# vco_main.net
KiCad netlist of a schematic drawn in EAGLE
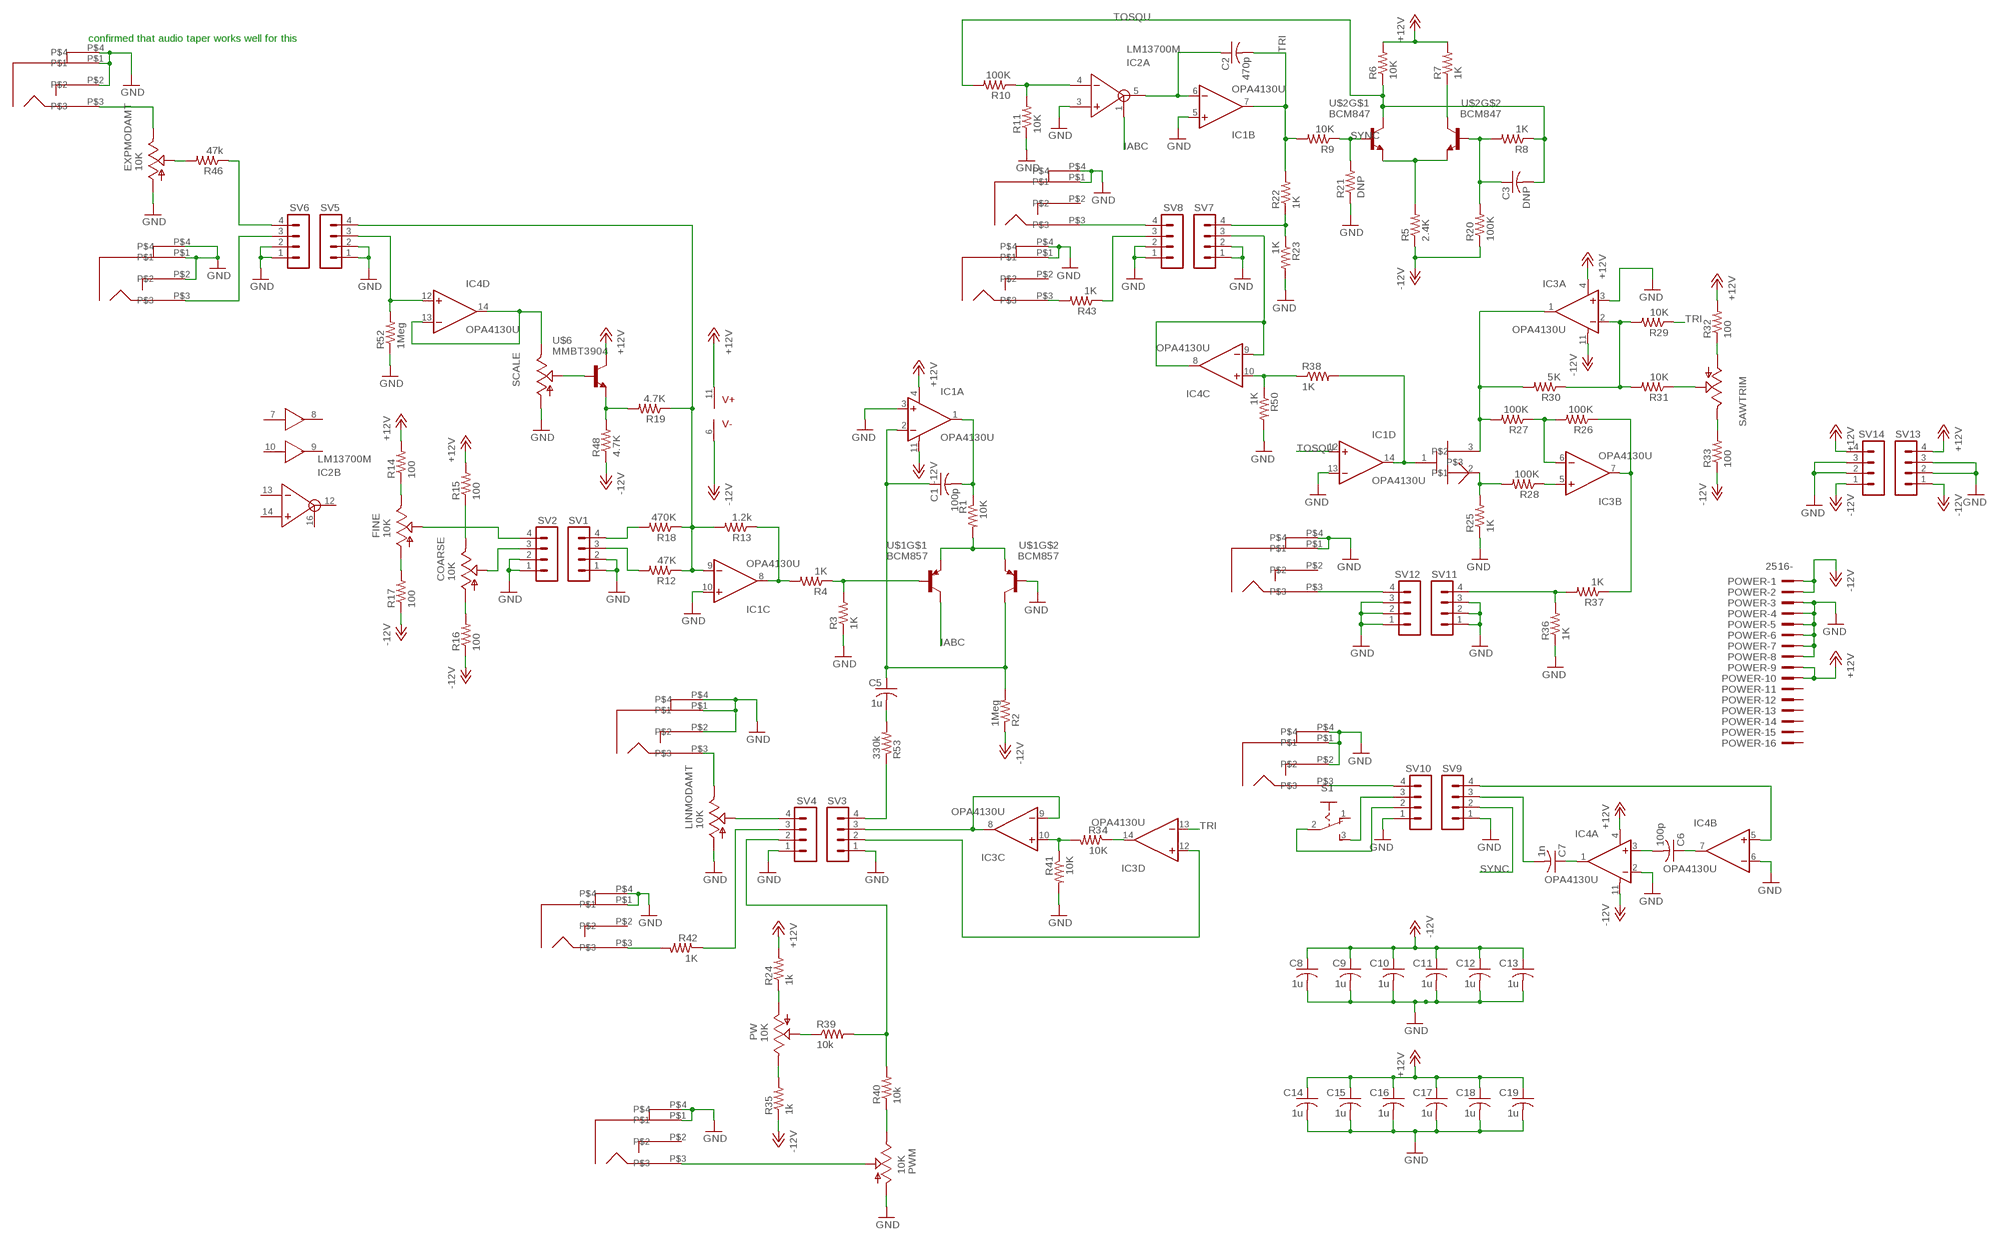
[diagram p0: schematic, sheet 1]

(export (version "E")
  (design (tool "Eeschema 10.0.6"))
  (components
    (comp (ref "C1")
      (value "100p")
      (footprint "eagle-import:C0603")
      (libsource (lib "eagle-import") (part "C-USC0603"))
    )
    (comp (ref "C2")
      (value "470p")
      (footprint "eagle-import:C0603")
      (libsource (lib "eagle-import") (part "C-USC0603"))
    )
    (comp (ref "C3")
      (value "DNP")
      (footprint "eagle-import:C0603")
      (libsource (lib "eagle-import") (part "C-USC0603"))
    )
    (comp (ref "C5")
      (value "1u")
      (footprint "eagle-import:C0603")
      (libsource (lib "eagle-import") (part "C-USC0603"))
    )
    (comp (ref "C6")
      (value "100p")
      (footprint "eagle-import:C0603")
      (libsource (lib "eagle-import") (part "C-USC0603"))
    )
    (comp (ref "C7")
      (value "1n")
      (footprint "eagle-import:C0603")
      (libsource (lib "eagle-import") (part "C-USC0603"))
    )
    (comp (ref "C8")
      (value "1u")
      (footprint "eagle-import:C0603")
      (libsource (lib "eagle-import") (part "C-USC0603"))
    )
    (comp (ref "C9")
      (value "1u")
      (footprint "eagle-import:C0603")
      (libsource (lib "eagle-import") (part "C-USC0603"))
    )
    (comp (ref "C10")
      (value "1u")
      (footprint "eagle-import:C0603")
      (libsource (lib "eagle-import") (part "C-USC0603"))
    )
    (comp (ref "C11")
      (value "1u")
      (footprint "eagle-import:C0603")
      (libsource (lib "eagle-import") (part "C-USC0603"))
    )
    (comp (ref "C12")
      (value "1u")
      (footprint "eagle-import:C0603")
      (libsource (lib "eagle-import") (part "C-USC0603"))
    )
    (comp (ref "C13")
      (value "1u")
      (footprint "eagle-import:C0603")
      (libsource (lib "eagle-import") (part "C-USC0603"))
    )
    (comp (ref "C14")
      (value "1u")
      (footprint "eagle-import:C0603")
      (libsource (lib "eagle-import") (part "C-USC0603"))
    )
    (comp (ref "C15")
      (value "1u")
      (footprint "eagle-import:C0603")
      (libsource (lib "eagle-import") (part "C-USC0603"))
    )
    (comp (ref "C16")
      (value "1u")
      (footprint "eagle-import:C0603")
      (libsource (lib "eagle-import") (part "C-USC0603"))
    )
    (comp (ref "C17")
      (value "1u")
      (footprint "eagle-import:C0603")
      (libsource (lib "eagle-import") (part "C-USC0603"))
    )
    (comp (ref "C18")
      (value "1u")
      (footprint "eagle-import:C0603")
      (libsource (lib "eagle-import") (part "C-USC0603"))
    )
    (comp (ref "C19")
      (value "1u")
      (footprint "eagle-import:C0603")
      (libsource (lib "eagle-import") (part "C-USC0603"))
    )
    (comp (ref "COARSE")
      (value "10K")
      (footprint "eagle-import:EVUFXJ")
      (libsource (lib "eagle-import") (part "US-EVUF2J"))
    )
    (comp (ref "EXPMOD")
      (value "PJ301BM")
      (footprint "eagle-import:PJ301BM")
      (libsource (lib "eagle-import") (part "PJ301BM"))
    )
    (comp (ref "EXPMODAMT")
      (value "10K")
      (footprint "eagle-import:EVUFXJ")
      (libsource (lib "eagle-import") (part "US-EVUF2J"))
    )
    (comp (ref "FINE")
      (value "10K")
      (footprint "eagle-import:EVUFXJ")
      (libsource (lib "eagle-import") (part "US-EVUF2J"))
    )
    (comp (ref "IC1")
      (value "OPA4130U")
      (footprint "eagle-import:SO14")
      (fields (field (name "MF") "TEXAS INSTRUMENTS") (field (name "MPN") "OPA4130UA"))
      (libsource (lib "eagle-import") (part "OPA4130U"))
    )
    (comp (ref "IC2")
      (value "LM13700M")
      (footprint "eagle-import:SO16")
      (libsource (lib "eagle-import") (part "LM13700M"))
    )
    (comp (ref "IC3")
      (value "OPA4130U")
      (footprint "eagle-import:SO14")
      (fields (field (name "MF") "TEXAS INSTRUMENTS") (field (name "MPN") "OPA4130UA"))
      (libsource (lib "eagle-import") (part "OPA4130U"))
    )
    (comp (ref "IC4")
      (value "OPA4130U")
      (footprint "eagle-import:SO14")
      (fields (field (name "MF") "TEXAS INSTRUMENTS") (field (name "MPN") "OPA4130UA"))
      (libsource (lib "eagle-import") (part "OPA4130U"))
    )
    (comp (ref "LINMOD")
      (value "PJ301BM")
      (footprint "eagle-import:PJ301BM")
      (libsource (lib "eagle-import") (part "PJ301BM"))
    )
    (comp (ref "LINMODAMT")
      (value "10K")
      (footprint "eagle-import:EVUFXJ")
      (libsource (lib "eagle-import") (part "US-EVUF2J"))
    )
    (comp (ref "POWER")
      (value "2516-")
      (footprint "eagle-import:PAK100_2500-16")
      (libsource (lib "eagle-import") (part "2516-"))
    )
    (comp (ref "PW")
      (value "10K")
      (footprint "eagle-import:EVUFXJ")
      (libsource (lib "eagle-import") (part "US-EVUF2J"))
    )
    (comp (ref "PWIN")
      (value "PJ301BM")
      (footprint "eagle-import:PJ301BM")
      (libsource (lib "eagle-import") (part "PJ301BM"))
    )
    (comp (ref "PWM")
      (value "10K")
      (footprint "eagle-import:EVUFXJ")
      (libsource (lib "eagle-import") (part "US-EVUF2J"))
    )
    (comp (ref "PWOUT")
      (value "PJ301BM")
      (footprint "eagle-import:PJ301BM")
      (libsource (lib "eagle-import") (part "PJ301BM"))
    )
    (comp (ref "R1")
      (value "10K")
      (footprint "eagle-import:R0603")
      (libsource (lib "eagle-import") (part "R-US_R0603"))
    )
    (comp (ref "R2")
      (value "1Meg")
      (footprint "eagle-import:R0603")
      (libsource (lib "eagle-import") (part "R-US_R0603"))
    )
    (comp (ref "R3")
      (value "1K")
      (footprint "eagle-import:R0603")
      (libsource (lib "eagle-import") (part "R-US_R0603"))
    )
    (comp (ref "R4")
      (value "1K")
      (footprint "eagle-import:R0603")
      (libsource (lib "eagle-import") (part "R-US_R0603"))
    )
    (comp (ref "R5")
      (value "2.4K")
      (footprint "eagle-import:R0603")
      (libsource (lib "eagle-import") (part "R-US_R0603"))
    )
    (comp (ref "R6")
      (value "10K")
      (footprint "eagle-import:R0603")
      (libsource (lib "eagle-import") (part "R-US_R0603"))
    )
    (comp (ref "R7")
      (value "1K")
      (footprint "eagle-import:R0603")
      (libsource (lib "eagle-import") (part "R-US_R0603"))
    )
    (comp (ref "R8")
      (value "1K")
      (footprint "eagle-import:R0603")
      (libsource (lib "eagle-import") (part "R-US_R0603"))
    )
    (comp (ref "R9")
      (value "10K")
      (footprint "eagle-import:R0603")
      (libsource (lib "eagle-import") (part "R-US_R0603"))
    )
    (comp (ref "R10")
      (value "100K")
      (footprint "eagle-import:R0603")
      (libsource (lib "eagle-import") (part "R-US_R0603"))
    )
    (comp (ref "R11")
      (value "10K")
      (footprint "eagle-import:R0603")
      (libsource (lib "eagle-import") (part "R-US_R0603"))
    )
    (comp (ref "R12")
      (value "47K")
      (footprint "eagle-import:R0603")
      (libsource (lib "eagle-import") (part "R-US_R0603"))
    )
    (comp (ref "R13")
      (value "1.2k")
      (footprint "eagle-import:R0603")
      (libsource (lib "eagle-import") (part "R-US_R0603"))
    )
    (comp (ref "R14")
      (value "100")
      (footprint "eagle-import:R0603")
      (libsource (lib "eagle-import") (part "R-US_R0603"))
    )
    (comp (ref "R15")
      (value "100")
      (footprint "eagle-import:R0603")
      (libsource (lib "eagle-import") (part "R-US_R0603"))
    )
    (comp (ref "R16")
      (value "100")
      (footprint "eagle-import:R0603")
      (libsource (lib "eagle-import") (part "R-US_R0603"))
    )
    (comp (ref "R17")
      (value "100")
      (footprint "eagle-import:R0603")
      (libsource (lib "eagle-import") (part "R-US_R0603"))
    )
    (comp (ref "R18")
      (value "470K")
      (footprint "eagle-import:R0603")
      (libsource (lib "eagle-import") (part "R-US_R0603"))
    )
    (comp (ref "R19")
      (value "4.7K")
      (footprint "eagle-import:R0603")
      (libsource (lib "eagle-import") (part "R-US_R0603"))
    )
    (comp (ref "R20")
      (value "100K")
      (footprint "eagle-import:R0603")
      (libsource (lib "eagle-import") (part "R-US_R0603"))
    )
    (comp (ref "R21")
      (value "DNP")
      (footprint "eagle-import:R0603")
      (libsource (lib "eagle-import") (part "R-US_R0603"))
    )
    (comp (ref "R22")
      (value "1K")
      (footprint "eagle-import:R0603")
      (libsource (lib "eagle-import") (part "R-US_R0603"))
    )
    (comp (ref "R23")
      (value "1K")
      (footprint "eagle-import:R0603")
      (libsource (lib "eagle-import") (part "R-US_R0603"))
    )
    (comp (ref "R24")
      (value "1k")
      (footprint "eagle-import:R0603")
      (libsource (lib "eagle-import") (part "R-US_R0603"))
    )
    (comp (ref "R25")
      (value "1K")
      (footprint "eagle-import:R0603")
      (libsource (lib "eagle-import") (part "R-US_R0603"))
    )
    (comp (ref "R26")
      (value "100K")
      (footprint "eagle-import:R0603")
      (libsource (lib "eagle-import") (part "R-US_R0603"))
    )
    (comp (ref "R27")
      (value "100K")
      (footprint "eagle-import:R0603")
      (libsource (lib "eagle-import") (part "R-US_R0603"))
    )
    (comp (ref "R28")
      (value "100K")
      (footprint "eagle-import:R0603")
      (libsource (lib "eagle-import") (part "R-US_R0603"))
    )
    (comp (ref "R29")
      (value "10K")
      (footprint "eagle-import:R0603")
      (libsource (lib "eagle-import") (part "R-US_R0603"))
    )
    (comp (ref "R30")
      (value "5K")
      (footprint "eagle-import:R0603")
      (libsource (lib "eagle-import") (part "R-US_R0603"))
    )
    (comp (ref "R31")
      (value "10K")
      (footprint "eagle-import:R0603")
      (libsource (lib "eagle-import") (part "R-US_R0603"))
    )
    (comp (ref "R32")
      (value "100")
      (footprint "eagle-import:R0603")
      (libsource (lib "eagle-import") (part "R-US_R0603"))
    )
    (comp (ref "R33")
      (value "100")
      (footprint "eagle-import:R0603")
      (libsource (lib "eagle-import") (part "R-US_R0603"))
    )
    (comp (ref "R34")
      (value "10K")
      (footprint "eagle-import:R0603")
      (libsource (lib "eagle-import") (part "R-US_R0603"))
    )
    (comp (ref "R35")
      (value "1k")
      (footprint "eagle-import:R0603")
      (libsource (lib "eagle-import") (part "R-US_R0603"))
    )
    (comp (ref "R36")
      (value "1K")
      (footprint "eagle-import:R0603")
      (libsource (lib "eagle-import") (part "R-US_R0603"))
    )
    (comp (ref "R37")
      (value "1K")
      (footprint "eagle-import:R0603")
      (libsource (lib "eagle-import") (part "R-US_R0603"))
    )
    (comp (ref "R38")
      (value "1K")
      (footprint "eagle-import:R0603")
      (libsource (lib "eagle-import") (part "R-US_R0603"))
    )
    (comp (ref "R39")
      (value "10k")
      (footprint "eagle-import:R0603")
      (libsource (lib "eagle-import") (part "R-US_R0603"))
    )
    (comp (ref "R40")
      (value "10k")
      (footprint "eagle-import:R0603")
      (libsource (lib "eagle-import") (part "R-US_R0603"))
    )
    (comp (ref "R41")
      (value "10K")
      (footprint "eagle-import:R0603")
      (libsource (lib "eagle-import") (part "R-US_R0603"))
    )
    (comp (ref "R42")
      (value "1K")
      (footprint "eagle-import:R0603")
      (libsource (lib "eagle-import") (part "R-US_R0603"))
    )
    (comp (ref "R43")
      (value "1K")
      (footprint "eagle-import:R0603")
      (libsource (lib "eagle-import") (part "R-US_R0603"))
    )
    (comp (ref "R46")
      (value "47k")
      (footprint "eagle-import:R0603")
      (libsource (lib "eagle-import") (part "R-US_R0603"))
    )
    (comp (ref "R48")
      (value "4.7K")
      (footprint "eagle-import:R0603")
      (libsource (lib "eagle-import") (part "R-US_R0603"))
    )
    (comp (ref "R50")
      (value "1K")
      (footprint "eagle-import:R0603")
      (libsource (lib "eagle-import") (part "R-US_R0603"))
    )
    (comp (ref "R52")
      (value "1Meg")
      (footprint "eagle-import:R0603")
      (libsource (lib "eagle-import") (part "R-US_R0603"))
    )
    (comp (ref "R53")
      (value "330k")
      (footprint "eagle-import:R0603")
      (libsource (lib "eagle-import") (part "R-US_R0603"))
    )
    (comp (ref "S1")
      (value "255SB")
      (footprint "eagle-import:255SB")
      (libsource (lib "eagle-import") (part "255SB"))
    )
    (comp (ref "SAW")
      (value "PJ301BM")
      (footprint "eagle-import:PJ301BM")
      (libsource (lib "eagle-import") (part "PJ301BM"))
    )
    (comp (ref "SAWTRIM")
      (value "TRIM_US-B64Y")
      (footprint "eagle-import:B64Y")
      (libsource (lib "eagle-import") (part "TRIM_US-B64Y"))
    )
    (comp (ref "SCALE")
      (value "TRIM_US-B64Y")
      (footprint "eagle-import:B64Y")
      (libsource (lib "eagle-import") (part "TRIM_US-B64Y"))
    )
    (comp (ref "SQUARE")
      (value "PJ301BM")
      (footprint "eagle-import:PJ301BM")
      (libsource (lib "eagle-import") (part "PJ301BM"))
    )
    (comp (ref "SV1")
      (value "MA04-1")
      (footprint "eagle-import:MA04-1")
      (libsource (lib "eagle-import") (part "MA04-1"))
    )
    (comp (ref "SV2")
      (value "MA04-1")
      (footprint "eagle-import:MA04-1")
      (libsource (lib "eagle-import") (part "MA04-1"))
    )
    (comp (ref "SV3")
      (value "MA04-1")
      (footprint "eagle-import:MA04-1")
      (libsource (lib "eagle-import") (part "MA04-1"))
    )
    (comp (ref "SV4")
      (value "MA04-1")
      (footprint "eagle-import:MA04-1")
      (libsource (lib "eagle-import") (part "MA04-1"))
    )
    (comp (ref "SV5")
      (value "MA04-1")
      (footprint "eagle-import:MA04-1")
      (libsource (lib "eagle-import") (part "MA04-1"))
    )
    (comp (ref "SV6")
      (value "MA04-1")
      (footprint "eagle-import:MA04-1")
      (libsource (lib "eagle-import") (part "MA04-1"))
    )
    (comp (ref "SV7")
      (value "MA04-1")
      (footprint "eagle-import:MA04-1")
      (libsource (lib "eagle-import") (part "MA04-1"))
    )
    (comp (ref "SV8")
      (value "MA04-1")
      (footprint "eagle-import:MA04-1")
      (libsource (lib "eagle-import") (part "MA04-1"))
    )
    (comp (ref "SV9")
      (value "MA04-1")
      (footprint "eagle-import:MA04-1")
      (libsource (lib "eagle-import") (part "MA04-1"))
    )
    (comp (ref "SV10")
      (value "MA04-1")
      (footprint "eagle-import:MA04-1")
      (libsource (lib "eagle-import") (part "MA04-1"))
    )
    (comp (ref "SV11")
      (value "MA04-1")
      (footprint "eagle-import:MA04-1")
      (libsource (lib "eagle-import") (part "MA04-1"))
    )
    (comp (ref "SV12")
      (value "MA04-1")
      (footprint "eagle-import:MA04-1")
      (libsource (lib "eagle-import") (part "MA04-1"))
    )
    (comp (ref "SV13")
      (value "MA04-1")
      (footprint "eagle-import:MA04-1")
      (libsource (lib "eagle-import") (part "MA04-1"))
    )
    (comp (ref "SV14")
      (value "MA04-1")
      (footprint "eagle-import:MA04-1")
      (libsource (lib "eagle-import") (part "MA04-1"))
    )
    (comp (ref "SYNC")
      (value "PJ301BM")
      (footprint "eagle-import:PJ301BM")
      (libsource (lib "eagle-import") (part "PJ301BM"))
    )
    (comp (ref "TRIOUT")
      (value "PJ301BM")
      (footprint "eagle-import:PJ301BM")
      (libsource (lib "eagle-import") (part "PJ301BM"))
    )
    (comp (ref "U$1")
      (value "BCM857")
      (footprint "eagle-import:SOT457R_PHILIPS")
      (libsource (lib "eagle-import") (part "BCM857"))
    )
    (comp (ref "U$2")
      (value "BCM847")
      (footprint "eagle-import:SOT457R_PHILIPS")
      (libsource (lib "eagle-import") (part "BCM847"))
    )
    (comp (ref "U$3")
      (value "2N7000")
      (footprint "eagle-import:SOT23")
      (libsource (lib "eagle-import") (part "2N7000"))
    )
    (comp (ref "U$6")
      (value "MMBT3904")
      (footprint "eagle-import:SOT23")
      (libsource (lib "eagle-import") (part "MMBT3904"))
    )
    (comp (ref "VPEROCT")
      (value "PJ301BM")
      (footprint "eagle-import:PJ301BM")
      (libsource (lib "eagle-import") (part "PJ301BM"))
    )
  )
  (nets
    (net (code "1") (name "+12V") (class "Default")
      (node (ref "C14") (pin "1") (pinfunction "1_1") (pintype "passive"))
      (node (ref "C15") (pin "1") (pinfunction "1_1") (pintype "passive"))
      (node (ref "C16") (pin "1") (pinfunction "1_1") (pintype "passive"))
      (node (ref "C17") (pin "1") (pinfunction "1_1") (pintype "passive"))
      (node (ref "C18") (pin "1") (pinfunction "1_1") (pintype "passive"))
      (node (ref "C19") (pin "1") (pinfunction "1_1") (pintype "passive"))
      (node (ref "IC1") (pin "4") (pinfunction "V+_4") (pintype "power_in"))
      (node (ref "IC2") (pin "11") (pinfunction "V+_11") (pintype "bidirectional"))
      (node (ref "IC3") (pin "4") (pinfunction "V+_4") (pintype "power_in"))
      (node (ref "IC4") (pin "4") (pinfunction "V+_4") (pintype "power_in"))
      (node (ref "POWER") (pin "10") (pinfunction "KL_10") (pintype "passive"))
      (node (ref "POWER") (pin "9") (pinfunction "KL_9") (pintype "passive"))
      (node (ref "R14") (pin "2") (pinfunction "2_2") (pintype "passive"))
      (node (ref "R15") (pin "2") (pinfunction "2_2") (pintype "passive"))
      (node (ref "R24") (pin "2") (pinfunction "2_2") (pintype "passive"))
      (node (ref "R32") (pin "2") (pinfunction "2_2") (pintype "passive"))
      (node (ref "R6") (pin "2") (pinfunction "2_2") (pintype "passive"))
      (node (ref "R7") (pin "2") (pinfunction "2_2") (pintype "passive"))
      (node (ref "SV13") (pin "4") (pinfunction "4_4") (pintype "passive"))
      (node (ref "SV14") (pin "4") (pinfunction "4_4") (pintype "passive"))
      (node (ref "U$6") (pin "3") (pinfunction "C_3") (pintype "passive"))
    )
    (net (code "2") (name "-12V") (class "Default")
      (node (ref "C10") (pin "1") (pinfunction "1_1") (pintype "passive"))
      (node (ref "C11") (pin "1") (pinfunction "1_1") (pintype "passive"))
      (node (ref "C12") (pin "1") (pinfunction "1_1") (pintype "passive"))
      (node (ref "C13") (pin "1") (pinfunction "1_1") (pintype "passive"))
      (node (ref "C8") (pin "1") (pinfunction "1_1") (pintype "passive"))
      (node (ref "C9") (pin "1") (pinfunction "1_1") (pintype "passive"))
      (node (ref "IC1") (pin "11") (pinfunction "V-_11") (pintype "power_in"))
      (node (ref "IC2") (pin "6") (pinfunction "V-_6") (pintype "bidirectional"))
      (node (ref "IC3") (pin "11") (pinfunction "V-_11") (pintype "power_in"))
      (node (ref "IC4") (pin "11") (pinfunction "V-_11") (pintype "power_in"))
      (node (ref "POWER") (pin "1") (pinfunction "KL_1") (pintype "passive"))
      (node (ref "POWER") (pin "2") (pinfunction "KL_2") (pintype "passive"))
      (node (ref "R16") (pin "1") (pinfunction "1_1") (pintype "passive"))
      (node (ref "R17") (pin "1") (pinfunction "1_1") (pintype "passive"))
      (node (ref "R2") (pin "1") (pinfunction "1_1") (pintype "passive"))
      (node (ref "R20") (pin "1") (pinfunction "1_1") (pintype "passive"))
      (node (ref "R33") (pin "1") (pinfunction "1_1") (pintype "passive"))
      (node (ref "R35") (pin "1") (pinfunction "1_1") (pintype "passive"))
      (node (ref "R48") (pin "1") (pinfunction "1_1") (pintype "passive"))
      (node (ref "R5") (pin "1") (pinfunction "1_1") (pintype "passive"))
      (node (ref "SV13") (pin "1") (pinfunction "1_1") (pintype "passive"))
      (node (ref "SV14") (pin "1") (pinfunction "1_1") (pintype "passive"))
    )
    (net (code "3") (name "/IABC") (class "Default")
      (node (ref "IC2") (pin "1") (pinfunction "IABC_1") (pintype "bidirectional"))
      (node (ref "U$1") (pin "6") (pinfunction "C_6") (pintype "passive"))
    )
    (net (code "4") (name "/SYNC") (class "Default")
      (node (ref "R21") (pin "2") (pinfunction "2_2") (pintype "passive"))
      (node (ref "R9") (pin "1") (pinfunction "1_1") (pintype "passive"))
      (node (ref "SV9") (pin "2") (pinfunction "2_2") (pintype "passive"))
      (node (ref "U$2") (pin "2") (pinfunction "B_2") (pintype "passive"))
    )
    (net (code "5") (name "/TOSQU") (class "Default")
      (node (ref "C3") (pin "2") (pinfunction "2_2") (pintype "passive"))
      (node (ref "IC1") (pin "12") (pinfunction "+IN_12") (pintype "input"))
      (node (ref "R10") (pin "2") (pinfunction "2_2") (pintype "passive"))
      (node (ref "R6") (pin "1") (pinfunction "1_1") (pintype "passive"))
      (node (ref "R8") (pin "1") (pinfunction "1_1") (pintype "passive"))
      (node (ref "U$2") (pin "6") (pinfunction "C_6") (pintype "passive"))
    )
    (net (code "6") (name "/TRI") (class "Default")
      (node (ref "C2") (pin "2") (pinfunction "2_2") (pintype "passive"))
      (node (ref "IC1") (pin "7") (pinfunction "OUT_7") (pintype "output"))
      (node (ref "IC3") (pin "13") (pinfunction "-IN_13") (pintype "input"))
      (node (ref "R22") (pin "2") (pinfunction "2_2") (pintype "passive"))
      (node (ref "R29") (pin "1") (pinfunction "1_1") (pintype "passive"))
      (node (ref "R9") (pin "2") (pinfunction "2_2") (pintype "passive"))
    )
    (net (code "7") (name "GND") (class "Default")
      (node (ref "C10") (pin "2") (pinfunction "2_2") (pintype "passive"))
      (node (ref "C11") (pin "2") (pinfunction "2_2") (pintype "passive"))
      (node (ref "C12") (pin "2") (pinfunction "2_2") (pintype "passive"))
      (node (ref "C13") (pin "2") (pinfunction "2_2") (pintype "passive"))
      (node (ref "C14") (pin "2") (pinfunction "2_2") (pintype "passive"))
      (node (ref "C15") (pin "2") (pinfunction "2_2") (pintype "passive"))
      (node (ref "C16") (pin "2") (pinfunction "2_2") (pintype "passive"))
      (node (ref "C17") (pin "2") (pinfunction "2_2") (pintype "passive"))
      (node (ref "C18") (pin "2") (pinfunction "2_2") (pintype "passive"))
      (node (ref "C19") (pin "2") (pinfunction "2_2") (pintype "passive"))
      (node (ref "C8") (pin "2") (pinfunction "2_2") (pintype "passive"))
      (node (ref "C9") (pin "2") (pinfunction "2_2") (pintype "passive"))
      (node (ref "EXPMOD") (pin "P$1") (pinfunction "P$1_P$1") (pintype "bidirectional"))
      (node (ref "EXPMOD") (pin "P$2") (pinfunction "P$2_P$2") (pintype "bidirectional"))
      (node (ref "EXPMOD") (pin "P$4") (pinfunction "P$4_P$4") (pintype "bidirectional"))
      (node (ref "EXPMODAMT") (pin "1") (pinfunction "A_1") (pintype "passive"))
      (node (ref "IC1") (pin "10") (pinfunction "+IN_10") (pintype "input"))
      (node (ref "IC1") (pin "13") (pinfunction "-IN_13") (pintype "input"))
      (node (ref "IC1") (pin "3") (pinfunction "+IN_3") (pintype "input"))
      (node (ref "IC1") (pin "5") (pinfunction "+IN_5") (pintype "input"))
      (node (ref "IC2") (pin "3") (pinfunction "+IN_3") (pintype "bidirectional"))
      (node (ref "IC3") (pin "3") (pinfunction "+IN_3") (pintype "input"))
      (node (ref "IC4") (pin "2") (pinfunction "-IN_2") (pintype "input"))
      (node (ref "IC4") (pin "6") (pinfunction "-IN_6") (pintype "input"))
      (node (ref "LINMOD") (pin "P$1") (pinfunction "P$1_P$1") (pintype "bidirectional"))
      (node (ref "LINMOD") (pin "P$2") (pinfunction "P$2_P$2") (pintype "bidirectional"))
      (node (ref "LINMOD") (pin "P$4") (pinfunction "P$4_P$4") (pintype "bidirectional"))
      (node (ref "LINMODAMT") (pin "1") (pinfunction "A_1") (pintype "passive"))
      (node (ref "POWER") (pin "3") (pinfunction "KL_3") (pintype "passive"))
      (node (ref "POWER") (pin "4") (pinfunction "KL_4") (pintype "passive"))
      (node (ref "POWER") (pin "5") (pinfunction "KL_5") (pintype "passive"))
      (node (ref "POWER") (pin "6") (pinfunction "KL_6") (pintype "passive"))
      (node (ref "POWER") (pin "7") (pinfunction "KL_7") (pintype "passive"))
      (node (ref "POWER") (pin "8") (pinfunction "KL_8") (pintype "passive"))
      (node (ref "PWIN") (pin "P$1") (pinfunction "P$1_P$1") (pintype "bidirectional"))
      (node (ref "PWIN") (pin "P$4") (pinfunction "P$4_P$4") (pintype "bidirectional"))
      (node (ref "PWM") (pin "1") (pinfunction "A_1") (pintype "passive"))
      (node (ref "PWOUT") (pin "P$1") (pinfunction "P$1_P$1") (pintype "bidirectional"))
      (node (ref "PWOUT") (pin "P$4") (pinfunction "P$4_P$4") (pintype "bidirectional"))
      (node (ref "R11") (pin "1") (pinfunction "1_1") (pintype "passive"))
      (node (ref "R21") (pin "1") (pinfunction "1_1") (pintype "passive"))
      (node (ref "R23") (pin "2") (pinfunction "2_2") (pintype "passive"))
      (node (ref "R25") (pin "1") (pinfunction "1_1") (pintype "passive"))
      (node (ref "R3") (pin "1") (pinfunction "1_1") (pintype "passive"))
      (node (ref "R36") (pin "1") (pinfunction "1_1") (pintype "passive"))
      (node (ref "R41") (pin "2") (pinfunction "2_2") (pintype "passive"))
      (node (ref "R50") (pin "2") (pinfunction "2_2") (pintype "passive"))
      (node (ref "R52") (pin "1") (pinfunction "1_1") (pintype "passive"))
      (node (ref "SAW") (pin "P$1") (pinfunction "P$1_P$1") (pintype "bidirectional"))
      (node (ref "SAW") (pin "P$4") (pinfunction "P$4_P$4") (pintype "bidirectional"))
      (node (ref "SCALE") (pin "A") (pinfunction "A_A") (pintype "passive"))
      (node (ref "SQUARE") (pin "P$1") (pinfunction "P$1_P$1") (pintype "bidirectional"))
      (node (ref "SQUARE") (pin "P$4") (pinfunction "P$4_P$4") (pintype "bidirectional"))
      (node (ref "SV1") (pin "1") (pinfunction "1_1") (pintype "passive"))
      (node (ref "SV1") (pin "2") (pinfunction "2_2") (pintype "passive"))
      (node (ref "SV10") (pin "1") (pinfunction "1_1") (pintype "passive"))
      (node (ref "SV11") (pin "1") (pinfunction "1_1") (pintype "passive"))
      (node (ref "SV11") (pin "2") (pinfunction "2_2") (pintype "passive"))
      (node (ref "SV11") (pin "3") (pinfunction "3_3") (pintype "passive"))
      (node (ref "SV12") (pin "1") (pinfunction "1_1") (pintype "passive"))
      (node (ref "SV12") (pin "2") (pinfunction "2_2") (pintype "passive"))
      (node (ref "SV12") (pin "3") (pinfunction "3_3") (pintype "passive"))
      (node (ref "SV13") (pin "2") (pinfunction "2_2") (pintype "passive"))
      (node (ref "SV13") (pin "3") (pinfunction "3_3") (pintype "passive"))
      (node (ref "SV14") (pin "2") (pinfunction "2_2") (pintype "passive"))
      (node (ref "SV14") (pin "3") (pinfunction "3_3") (pintype "passive"))
      (node (ref "SV2") (pin "1") (pinfunction "1_1") (pintype "passive"))
      (node (ref "SV2") (pin "2") (pinfunction "2_2") (pintype "passive"))
      (node (ref "SV3") (pin "1") (pinfunction "1_1") (pintype "passive"))
      (node (ref "SV4") (pin "1") (pinfunction "1_1") (pintype "passive"))
      (node (ref "SV5") (pin "1") (pinfunction "1_1") (pintype "passive"))
      (node (ref "SV5") (pin "2") (pinfunction "2_2") (pintype "passive"))
      (node (ref "SV6") (pin "1") (pinfunction "1_1") (pintype "passive"))
      (node (ref "SV6") (pin "2") (pinfunction "2_2") (pintype "passive"))
      (node (ref "SV7") (pin "1") (pinfunction "1_1") (pintype "passive"))
      (node (ref "SV7") (pin "2") (pinfunction "2_2") (pintype "passive"))
      (node (ref "SV8") (pin "1") (pinfunction "1_1") (pintype "passive"))
      (node (ref "SV8") (pin "2") (pinfunction "2_2") (pintype "passive"))
      (node (ref "SV9") (pin "1") (pinfunction "1_1") (pintype "passive"))
      (node (ref "SYNC") (pin "P$1") (pinfunction "P$1_P$1") (pintype "bidirectional"))
      (node (ref "SYNC") (pin "P$2") (pinfunction "P$2_P$2") (pintype "bidirectional"))
      (node (ref "SYNC") (pin "P$4") (pinfunction "P$4_P$4") (pintype "bidirectional"))
      (node (ref "TRIOUT") (pin "P$1") (pinfunction "P$1_P$1") (pintype "bidirectional"))
      (node (ref "TRIOUT") (pin "P$4") (pinfunction "P$4_P$4") (pintype "bidirectional"))
      (node (ref "U$1") (pin "5") (pinfunction "B_5") (pintype "passive"))
      (node (ref "VPEROCT") (pin "P$1") (pinfunction "P$1_P$1") (pintype "bidirectional"))
      (node (ref "VPEROCT") (pin "P$2") (pinfunction "P$2_P$2") (pintype "bidirectional"))
      (node (ref "VPEROCT") (pin "P$4") (pinfunction "P$4_P$4") (pintype "bidirectional"))
    )
    (net (code "8") (name "Net-(C5-Pad2)") (class "Default")
      (node (ref "C5") (pin "2") (pinfunction "2_2") (pintype "passive"))
      (node (ref "R53") (pin "2") (pinfunction "2_2") (pintype "passive"))
    )
    (net (code "9") (name "Net-(C7-Pad2)") (class "Default")
      (node (ref "C7") (pin "2") (pinfunction "2_2") (pintype "passive"))
      (node (ref "SV9") (pin "3") (pinfunction "3_3") (pintype "passive"))
    )
    (net (code "10") (name "Net-(COARSE-A)") (class "Default")
      (node (ref "COARSE") (pin "1") (pinfunction "A_1") (pintype "passive"))
      (node (ref "R16") (pin "2") (pinfunction "2_2") (pintype "passive"))
    )
    (net (code "11") (name "Net-(COARSE-E)") (class "Default")
      (node (ref "COARSE") (pin "3") (pinfunction "E_3") (pintype "passive"))
      (node (ref "R15") (pin "1") (pinfunction "1_1") (pintype "passive"))
    )
    (net (code "12") (name "Net-(COARSE-S)") (class "Default")
      (node (ref "COARSE") (pin "2") (pinfunction "S_2") (pintype "passive"))
      (node (ref "SV2") (pin "3") (pinfunction "3_3") (pintype "passive"))
    )
    (net (code "13") (name "Net-(EXPMODAMT-E)") (class "Default")
      (node (ref "EXPMOD") (pin "P$3") (pinfunction "P$3_P$3") (pintype "bidirectional"))
      (node (ref "EXPMODAMT") (pin "3") (pinfunction "E_3") (pintype "passive"))
    )
    (net (code "14") (name "Net-(EXPMODAMT-S)") (class "Default")
      (node (ref "EXPMODAMT") (pin "2") (pinfunction "S_2") (pintype "passive"))
      (node (ref "R46") (pin "2") (pinfunction "2_2") (pintype "passive"))
    )
    (net (code "15") (name "Net-(FINE-A)") (class "Default")
      (node (ref "FINE") (pin "1") (pinfunction "A_1") (pintype "passive"))
      (node (ref "R17") (pin "2") (pinfunction "2_2") (pintype "passive"))
    )
    (net (code "16") (name "Net-(FINE-E)") (class "Default")
      (node (ref "FINE") (pin "3") (pinfunction "E_3") (pintype "passive"))
      (node (ref "R14") (pin "1") (pinfunction "1_1") (pintype "passive"))
    )
    (net (code "17") (name "Net-(FINE-S)") (class "Default")
      (node (ref "FINE") (pin "2") (pinfunction "S_2") (pintype "passive"))
      (node (ref "SV2") (pin "4") (pinfunction "4_4") (pintype "passive"))
    )
    (net (code "18") (name "Net-(IC1A--IN)") (class "Default")
      (node (ref "C1") (pin "1") (pinfunction "1_1") (pintype "passive"))
      (node (ref "C5") (pin "1") (pinfunction "1_1") (pintype "passive"))
      (node (ref "IC1") (pin "2") (pinfunction "-IN_2") (pintype "input"))
      (node (ref "R2") (pin "2") (pinfunction "2_2") (pintype "passive"))
      (node (ref "U$1") (pin "3") (pinfunction "C_3") (pintype "passive"))
    )
    (net (code "19") (name "Net-(IC1A-OUT)") (class "Default")
      (node (ref "C1") (pin "2") (pinfunction "2_2") (pintype "passive"))
      (node (ref "IC1") (pin "1") (pinfunction "OUT_1") (pintype "output"))
      (node (ref "R1") (pin "1") (pinfunction "1_1") (pintype "passive"))
    )
    (net (code "20") (name "Net-(IC1B--IN)") (class "Default")
      (node (ref "C2") (pin "1") (pinfunction "1_1") (pintype "passive"))
      (node (ref "IC1") (pin "6") (pinfunction "-IN_6") (pintype "input"))
      (node (ref "IC2") (pin "5") (pinfunction "OUT_5") (pintype "bidirectional"))
    )
    (net (code "21") (name "Net-(IC1C--IN)") (class "Default")
      (node (ref "IC1") (pin "9") (pinfunction "-IN_9") (pintype "input"))
      (node (ref "R12") (pin "1") (pinfunction "1_1") (pintype "passive"))
      (node (ref "R13") (pin "2") (pinfunction "2_2") (pintype "passive"))
      (node (ref "R18") (pin "1") (pinfunction "1_1") (pintype "passive"))
      (node (ref "R19") (pin "1") (pinfunction "1_1") (pintype "passive"))
      (node (ref "SV5") (pin "4") (pinfunction "4_4") (pintype "passive"))
    )
    (net (code "22") (name "Net-(IC1C-OUT)") (class "Default")
      (node (ref "IC1") (pin "8") (pinfunction "OUT_8") (pintype "output"))
      (node (ref "R13") (pin "1") (pinfunction "1_1") (pintype "passive"))
      (node (ref "R4") (pin "2") (pinfunction "2_2") (pintype "passive"))
    )
    (net (code "23") (name "Net-(IC1D-OUT)") (class "Default")
      (node (ref "IC1") (pin "14") (pinfunction "OUT_14") (pintype "output"))
      (node (ref "R38") (pin "2") (pinfunction "2_2") (pintype "passive"))
      (node (ref "U$3") (pin "1") (pinfunction "P$3_1") (pintype "bidirectional"))
    )
    (net (code "24") (name "Net-(IC2A--IN)") (class "Default")
      (node (ref "IC2") (pin "4") (pinfunction "-IN_4") (pintype "bidirectional"))
      (node (ref "R10") (pin "1") (pinfunction "1_1") (pintype "passive"))
      (node (ref "R11") (pin "2") (pinfunction "2_2") (pintype "passive"))
    )
    (net (code "25") (name "Net-(IC3A--IN)") (class "Default")
      (node (ref "IC3") (pin "2") (pinfunction "-IN_2") (pintype "input"))
      (node (ref "R29") (pin "2") (pinfunction "2_2") (pintype "passive"))
      (node (ref "R30") (pin "1") (pinfunction "1_1") (pintype "passive"))
      (node (ref "R31") (pin "2") (pinfunction "2_2") (pintype "passive"))
    )
    (net (code "26") (name "Net-(IC3A-OUT)") (class "Default")
      (node (ref "IC3") (pin "1") (pinfunction "OUT_1") (pintype "output"))
      (node (ref "R27") (pin "2") (pinfunction "2_2") (pintype "passive"))
      (node (ref "R30") (pin "2") (pinfunction "2_2") (pintype "passive"))
      (node (ref "U$3") (pin "3") (pinfunction "P$2_3") (pintype "bidirectional"))
    )
    (net (code "27") (name "Net-(IC3B-+IN)") (class "Default")
      (node (ref "IC3") (pin "5") (pinfunction "+IN_5") (pintype "input"))
      (node (ref "R28") (pin "1") (pinfunction "1_1") (pintype "passive"))
    )
    (net (code "28") (name "Net-(IC3B--IN)") (class "Default")
      (node (ref "IC3") (pin "6") (pinfunction "-IN_6") (pintype "input"))
      (node (ref "R26") (pin "2") (pinfunction "2_2") (pintype "passive"))
      (node (ref "R27") (pin "1") (pinfunction "1_1") (pintype "passive"))
    )
    (net (code "29") (name "Net-(IC3B-OUT)") (class "Default")
      (node (ref "IC3") (pin "7") (pinfunction "OUT_7") (pintype "output"))
      (node (ref "R26") (pin "1") (pinfunction "1_1") (pintype "passive"))
      (node (ref "R37") (pin "1") (pinfunction "1_1") (pintype "passive"))
    )
    (net (code "30") (name "Net-(IC3C-+IN)") (class "Default")
      (node (ref "IC3") (pin "10") (pinfunction "+IN_10") (pintype "input"))
      (node (ref "R34") (pin "2") (pinfunction "2_2") (pintype "passive"))
      (node (ref "R41") (pin "1") (pinfunction "1_1") (pintype "passive"))
    )
    (net (code "31") (name "Net-(IC3C--IN)") (class "Default")
      (node (ref "IC3") (pin "8") (pinfunction "OUT_8") (pintype "output"))
      (node (ref "IC3") (pin "9") (pinfunction "-IN_9") (pintype "input"))
      (node (ref "SV3") (pin "3") (pinfunction "3_3") (pintype "passive"))
    )
    (net (code "32") (name "Net-(IC3D-+IN)") (class "Default")
      (node (ref "IC3") (pin "12") (pinfunction "+IN_12") (pintype "input"))
      (node (ref "SV3") (pin "2") (pinfunction "2_2") (pintype "passive"))
    )
    (net (code "33") (name "Net-(IC3D-OUT)") (class "Default")
      (node (ref "IC3") (pin "14") (pinfunction "OUT_14") (pintype "output"))
      (node (ref "R34") (pin "1") (pinfunction "1_1") (pintype "passive"))
    )
    (net (code "34") (name "Net-(IC4A-+IN)") (class "Default")
      (node (ref "C6") (pin "2") (pinfunction "2_2") (pintype "passive"))
      (node (ref "IC4") (pin "3") (pinfunction "+IN_3") (pintype "input"))
    )
    (net (code "35") (name "Net-(IC4A-OUT)") (class "Default")
      (node (ref "C7") (pin "1") (pinfunction "1_1") (pintype "passive"))
      (node (ref "IC4") (pin "1") (pinfunction "OUT_1") (pintype "output"))
    )
    (net (code "36") (name "Net-(IC4B-+IN)") (class "Default")
      (node (ref "IC4") (pin "5") (pinfunction "+IN_5") (pintype "input"))
      (node (ref "SV9") (pin "4") (pinfunction "4_4") (pintype "passive"))
    )
    (net (code "37") (name "Net-(IC4B-OUT)") (class "Default")
      (node (ref "C6") (pin "1") (pinfunction "1_1") (pintype "passive"))
      (node (ref "IC4") (pin "7") (pinfunction "OUT_7") (pintype "output"))
    )
    (net (code "38") (name "Net-(IC4C-+IN)") (class "Default")
      (node (ref "IC4") (pin "10") (pinfunction "+IN_10") (pintype "input"))
      (node (ref "R38") (pin "1") (pinfunction "1_1") (pintype "passive"))
      (node (ref "R50") (pin "1") (pinfunction "1_1") (pintype "passive"))
    )
    (net (code "39") (name "Net-(IC4C--IN)") (class "Default")
      (node (ref "IC4") (pin "8") (pinfunction "OUT_8") (pintype "output"))
      (node (ref "IC4") (pin "9") (pinfunction "-IN_9") (pintype "input"))
      (node (ref "SV7") (pin "3") (pinfunction "3_3") (pintype "passive"))
    )
    (net (code "40") (name "Net-(IC4D-+IN)") (class "Default")
      (node (ref "IC4") (pin "12") (pinfunction "+IN_12") (pintype "input"))
      (node (ref "R52") (pin "2") (pinfunction "2_2") (pintype "passive"))
      (node (ref "SV5") (pin "3") (pinfunction "3_3") (pintype "passive"))
    )
    (net (code "41") (name "Net-(IC4D--IN)") (class "Default")
      (node (ref "IC4") (pin "13") (pinfunction "-IN_13") (pintype "input"))
      (node (ref "IC4") (pin "14") (pinfunction "OUT_14") (pintype "output"))
      (node (ref "SCALE") (pin "E") (pinfunction "E_E") (pintype "passive"))
    )
    (net (code "42") (name "Net-(LINMODAMT-E)") (class "Default")
      (node (ref "LINMOD") (pin "P$3") (pinfunction "P$3_P$3") (pintype "bidirectional"))
      (node (ref "LINMODAMT") (pin "3") (pinfunction "E_3") (pintype "passive"))
    )
    (net (code "43") (name "Net-(LINMODAMT-S)") (class "Default")
      (node (ref "LINMODAMT") (pin "2") (pinfunction "S_2") (pintype "passive"))
      (node (ref "SV4") (pin "4") (pinfunction "4_4") (pintype "passive"))
    )
    (net (code "44") (name "Net-(PW-A)") (class "Default")
      (node (ref "PW") (pin "1") (pinfunction "A_1") (pintype "passive"))
      (node (ref "R24") (pin "1") (pinfunction "1_1") (pintype "passive"))
    )
    (net (code "45") (name "Net-(PW-E)") (class "Default")
      (node (ref "PW") (pin "3") (pinfunction "E_3") (pintype "passive"))
      (node (ref "R35") (pin "2") (pinfunction "2_2") (pintype "passive"))
    )
    (net (code "46") (name "Net-(PW-S)") (class "Default")
      (node (ref "PW") (pin "2") (pinfunction "S_2") (pintype "passive"))
      (node (ref "R39") (pin "1") (pinfunction "1_1") (pintype "passive"))
    )
    (net (code "47") (name "Net-(PWM-E)") (class "Default")
      (node (ref "PWM") (pin "3") (pinfunction "E_3") (pintype "passive"))
      (node (ref "R40") (pin "1") (pinfunction "1_1") (pintype "passive"))
    )
    (net (code "48") (name "Net-(PWM-S)") (class "Default")
      (node (ref "PWIN") (pin "P$3") (pinfunction "P$3_P$3") (pintype "bidirectional"))
      (node (ref "PWM") (pin "2") (pinfunction "S_2") (pintype "passive"))
    )
    (net (code "49") (name "Net-(PWOUT-PadP$3)") (class "Default")
      (node (ref "PWOUT") (pin "P$3") (pinfunction "P$3_P$3") (pintype "bidirectional"))
      (node (ref "R42") (pin "2") (pinfunction "2_2") (pintype "passive"))
    )
    (net (code "50") (name "Net-(R12-Pad2)") (class "Default")
      (node (ref "R12") (pin "2") (pinfunction "2_2") (pintype "passive"))
      (node (ref "SV1") (pin "3") (pinfunction "3_3") (pintype "passive"))
    )
    (net (code "51") (name "Net-(R18-Pad2)") (class "Default")
      (node (ref "R18") (pin "2") (pinfunction "2_2") (pintype "passive"))
      (node (ref "SV1") (pin "4") (pinfunction "4_4") (pintype "passive"))
    )
    (net (code "52") (name "Net-(R22-Pad1)") (class "Default")
      (node (ref "R22") (pin "1") (pinfunction "1_1") (pintype "passive"))
      (node (ref "R23") (pin "1") (pinfunction "1_1") (pintype "passive"))
      (node (ref "SV7") (pin "4") (pinfunction "4_4") (pintype "passive"))
    )
    (net (code "53") (name "Net-(R31-Pad1)") (class "Default")
      (node (ref "R31") (pin "1") (pinfunction "1_1") (pintype "passive"))
      (node (ref "SAWTRIM") (pin "S") (pinfunction "S_S") (pintype "passive"))
    )
    (net (code "54") (name "Net-(R32-Pad1)") (class "Default")
      (node (ref "R32") (pin "1") (pinfunction "1_1") (pintype "passive"))
      (node (ref "SAWTRIM") (pin "A") (pinfunction "A_A") (pintype "passive"))
    )
    (net (code "55") (name "Net-(R33-Pad2)") (class "Default")
      (node (ref "R33") (pin "2") (pinfunction "2_2") (pintype "passive"))
      (node (ref "SAWTRIM") (pin "E") (pinfunction "E_E") (pintype "passive"))
    )
    (net (code "56") (name "Net-(R36-Pad2)") (class "Default")
      (node (ref "R36") (pin "2") (pinfunction "2_2") (pintype "passive"))
      (node (ref "R37") (pin "2") (pinfunction "2_2") (pintype "passive"))
      (node (ref "SV11") (pin "4") (pinfunction "4_4") (pintype "passive"))
    )
    (net (code "57") (name "Net-(R39-Pad2)") (class "Default")
      (node (ref "R39") (pin "2") (pinfunction "2_2") (pintype "passive"))
      (node (ref "R40") (pin "2") (pinfunction "2_2") (pintype "passive"))
      (node (ref "SV4") (pin "2") (pinfunction "2_2") (pintype "passive"))
    )
    (net (code "58") (name "Net-(R42-Pad1)") (class "Default")
      (node (ref "R42") (pin "1") (pinfunction "1_1") (pintype "passive"))
      (node (ref "SV4") (pin "3") (pinfunction "3_3") (pintype "passive"))
    )
    (net (code "59") (name "Net-(R43-Pad1)") (class "Default")
      (node (ref "R43") (pin "1") (pinfunction "1_1") (pintype "passive"))
      (node (ref "SV8") (pin "3") (pinfunction "3_3") (pintype "passive"))
    )
    (net (code "60") (name "Net-(R43-Pad2)") (class "Default")
      (node (ref "R43") (pin "2") (pinfunction "2_2") (pintype "passive"))
      (node (ref "SQUARE") (pin "P$3") (pinfunction "P$3_P$3") (pintype "bidirectional"))
    )
    (net (code "61") (name "Net-(R46-Pad1)") (class "Default")
      (node (ref "R46") (pin "1") (pinfunction "1_1") (pintype "passive"))
      (node (ref "SV6") (pin "4") (pinfunction "4_4") (pintype "passive"))
    )
    (net (code "62") (name "Net-(R53-Pad1)") (class "Default")
      (node (ref "R53") (pin "1") (pinfunction "1_1") (pintype "passive"))
      (node (ref "SV3") (pin "4") (pinfunction "4_4") (pintype "passive"))
    )
    (net (code "63") (name "Net-(S1-P)") (class "Default")
      (node (ref "S1") (pin "2") (pinfunction "P_2") (pintype "passive"))
      (node (ref "SV10") (pin "2") (pinfunction "2_2") (pintype "passive"))
    )
    (net (code "64") (name "Net-(S1-S)") (class "Default")
      (node (ref "S1") (pin "3") (pinfunction "S_3") (pintype "passive"))
      (node (ref "SV10") (pin "3") (pinfunction "3_3") (pintype "passive"))
    )
    (net (code "65") (name "Net-(SAW-PadP$3)") (class "Default")
      (node (ref "SAW") (pin "P$3") (pinfunction "P$3_P$3") (pintype "bidirectional"))
      (node (ref "SV12") (pin "4") (pinfunction "4_4") (pintype "passive"))
    )
    (net (code "66") (name "Net-(SV6-Pad3)") (class "Default")
      (node (ref "SV6") (pin "3") (pinfunction "3_3") (pintype "passive"))
      (node (ref "VPEROCT") (pin "P$3") (pinfunction "P$3_P$3") (pintype "bidirectional"))
    )
    (net (code "67") (name "Net-(SV8-Pad4)") (class "Default")
      (node (ref "SV8") (pin "4") (pinfunction "4_4") (pintype "passive"))
      (node (ref "TRIOUT") (pin "P$3") (pinfunction "P$3_P$3") (pintype "bidirectional"))
    )
    (net (code "68") (name "Net-(SV10-Pad4)") (class "Default")
      (node (ref "SV10") (pin "4") (pinfunction "4_4") (pintype "passive"))
      (node (ref "SYNC") (pin "P$3") (pinfunction "P$3_P$3") (pintype "bidirectional"))
    )
    (net (code "69") (name "Net-(U$1A-B)") (class "Default")
      (node (ref "R3") (pin "2") (pinfunction "2_2") (pintype "passive"))
      (node (ref "R4") (pin "1") (pinfunction "1_1") (pintype "passive"))
      (node (ref "U$1") (pin "2") (pinfunction "B_2") (pintype "passive"))
    )
    (net (code "70") (name "Net-(U$1A-E)") (class "Default")
      (node (ref "R1") (pin "2") (pinfunction "2_2") (pintype "passive"))
      (node (ref "U$1") (pin "1") (pinfunction "E_1") (pintype "passive"))
      (node (ref "U$1") (pin "4") (pinfunction "E_4") (pintype "passive"))
    )
    (net (code "71") (name "Net-(U$2A-E)") (class "Default")
      (node (ref "R5") (pin "2") (pinfunction "2_2") (pintype "passive"))
      (node (ref "U$2") (pin "1") (pinfunction "E_1") (pintype "passive"))
      (node (ref "U$2") (pin "4") (pinfunction "E_4") (pintype "passive"))
    )
    (net (code "72") (name "Net-(U$2B-B)") (class "Default")
      (node (ref "C3") (pin "1") (pinfunction "1_1") (pintype "passive"))
      (node (ref "R20") (pin "2") (pinfunction "2_2") (pintype "passive"))
      (node (ref "R8") (pin "2") (pinfunction "2_2") (pintype "passive"))
      (node (ref "U$2") (pin "5") (pinfunction "B_5") (pintype "passive"))
    )
    (net (code "73") (name "Net-(U$2B-C)") (class "Default")
      (node (ref "R7") (pin "1") (pinfunction "1_1") (pintype "passive"))
      (node (ref "U$2") (pin "3") (pinfunction "C_3") (pintype "passive"))
    )
    (net (code "74") (name "Net-(U$3-P$1)") (class "Default")
      (node (ref "R25") (pin "2") (pinfunction "2_2") (pintype "passive"))
      (node (ref "R28") (pin "2") (pinfunction "2_2") (pintype "passive"))
      (node (ref "U$3") (pin "2") (pinfunction "P$1_2") (pintype "bidirectional"))
    )
    (net (code "75") (name "Net-(U$6-B)") (class "Default")
      (node (ref "SCALE") (pin "S") (pinfunction "S_S") (pintype "passive"))
      (node (ref "U$6") (pin "1") (pinfunction "B_1") (pintype "passive"))
    )
    (net (code "76") (name "Net-(U$6-E)") (class "Default")
      (node (ref "R19") (pin "2") (pinfunction "2_2") (pintype "passive"))
      (node (ref "R48") (pin "2") (pinfunction "2_2") (pintype "passive"))
      (node (ref "U$6") (pin "2") (pinfunction "E_2") (pintype "passive"))
    )
    (net (code "77") (name "unconnected-(IC2B-+IN-Pad14)") (class "Default")
      (node (ref "IC2") (pin "14") (pinfunction "+IN_14") (pintype "bidirectional"))
    )
    (net (code "78") (name "unconnected-(IC2B--IN-Pad13)") (class "Default")
      (node (ref "IC2") (pin "13") (pinfunction "-IN_13") (pintype "bidirectional"))
    )
    (net (code "79") (name "unconnected-(IC2B-IABC-Pad16)") (class "Default")
      (node (ref "IC2") (pin "16") (pinfunction "IABC_16") (pintype "bidirectional"))
    )
    (net (code "80") (name "unconnected-(IC2B-OUT-Pad12)") (class "Default")
      (node (ref "IC2") (pin "12") (pinfunction "OUT_12") (pintype "bidirectional"))
    )
    (net (code "81") (name "unconnected-(IC2C-IN-Pad7)") (class "Default")
      (node (ref "IC2") (pin "7") (pinfunction "IN_7") (pintype "bidirectional"))
    )
    (net (code "82") (name "unconnected-(IC2C-OUT-Pad8)") (class "Default")
      (node (ref "IC2") (pin "8") (pinfunction "OUT_8") (pintype "bidirectional"))
    )
    (net (code "83") (name "unconnected-(IC2D-IN-Pad10)") (class "Default")
      (node (ref "IC2") (pin "10") (pinfunction "IN_10") (pintype "bidirectional"))
    )
    (net (code "84") (name "unconnected-(IC2D-OUT-Pad9)") (class "Default")
      (node (ref "IC2") (pin "9") (pinfunction "OUT_9") (pintype "bidirectional"))
    )
    (net (code "85") (name "unconnected-(POWERC-KL-Pad11)") (class "Default")
      (node (ref "POWER") (pin "11") (pinfunction "KL_11") (pintype "passive"))
    )
    (net (code "86") (name "unconnected-(POWERD-KL-Pad12)") (class "Default")
      (node (ref "POWER") (pin "12") (pinfunction "KL_12") (pintype "passive"))
    )
    (net (code "87") (name "unconnected-(POWERE-KL-Pad13)") (class "Default")
      (node (ref "POWER") (pin "13") (pinfunction "KL_13") (pintype "passive"))
    )
    (net (code "88") (name "unconnected-(POWERF-KL-Pad14)") (class "Default")
      (node (ref "POWER") (pin "14") (pinfunction "KL_14") (pintype "passive"))
    )
    (net (code "89") (name "unconnected-(POWERG-KL-Pad15)") (class "Default")
      (node (ref "POWER") (pin "15") (pinfunction "KL_15") (pintype "passive"))
    )
    (net (code "90") (name "unconnected-(POWERH-KL-Pad16)") (class "Default")
      (node (ref "POWER") (pin "16") (pinfunction "KL_16") (pintype "passive"))
    )
    (net (code "91") (name "unconnected-(PWIN-PadP$2)") (class "Default")
      (node (ref "PWIN") (pin "P$2") (pinfunction "P$2_P$2") (pintype "bidirectional"))
    )
    (net (code "92") (name "unconnected-(PWOUT-PadP$2)") (class "Default")
      (node (ref "PWOUT") (pin "P$2") (pinfunction "P$2_P$2") (pintype "bidirectional"))
    )
    (net (code "93") (name "unconnected-(S1-O-Pad1)") (class "Default")
      (node (ref "S1") (pin "1") (pinfunction "O_1") (pintype "passive"))
    )
    (net (code "94") (name "unconnected-(SAW-PadP$2)") (class "Default")
      (node (ref "SAW") (pin "P$2") (pinfunction "P$2_P$2") (pintype "bidirectional"))
    )
    (net (code "95") (name "unconnected-(SQUARE-PadP$2)") (class "Default")
      (node (ref "SQUARE") (pin "P$2") (pinfunction "P$2_P$2") (pintype "bidirectional"))
    )
    (net (code "96") (name "unconnected-(TRIOUT-PadP$2)") (class "Default")
      (node (ref "TRIOUT") (pin "P$2") (pinfunction "P$2_P$2") (pintype "bidirectional"))
    )
  )
)
